# pi_pcb.net
KiCad netlist of a schematic drawn in EAGLE
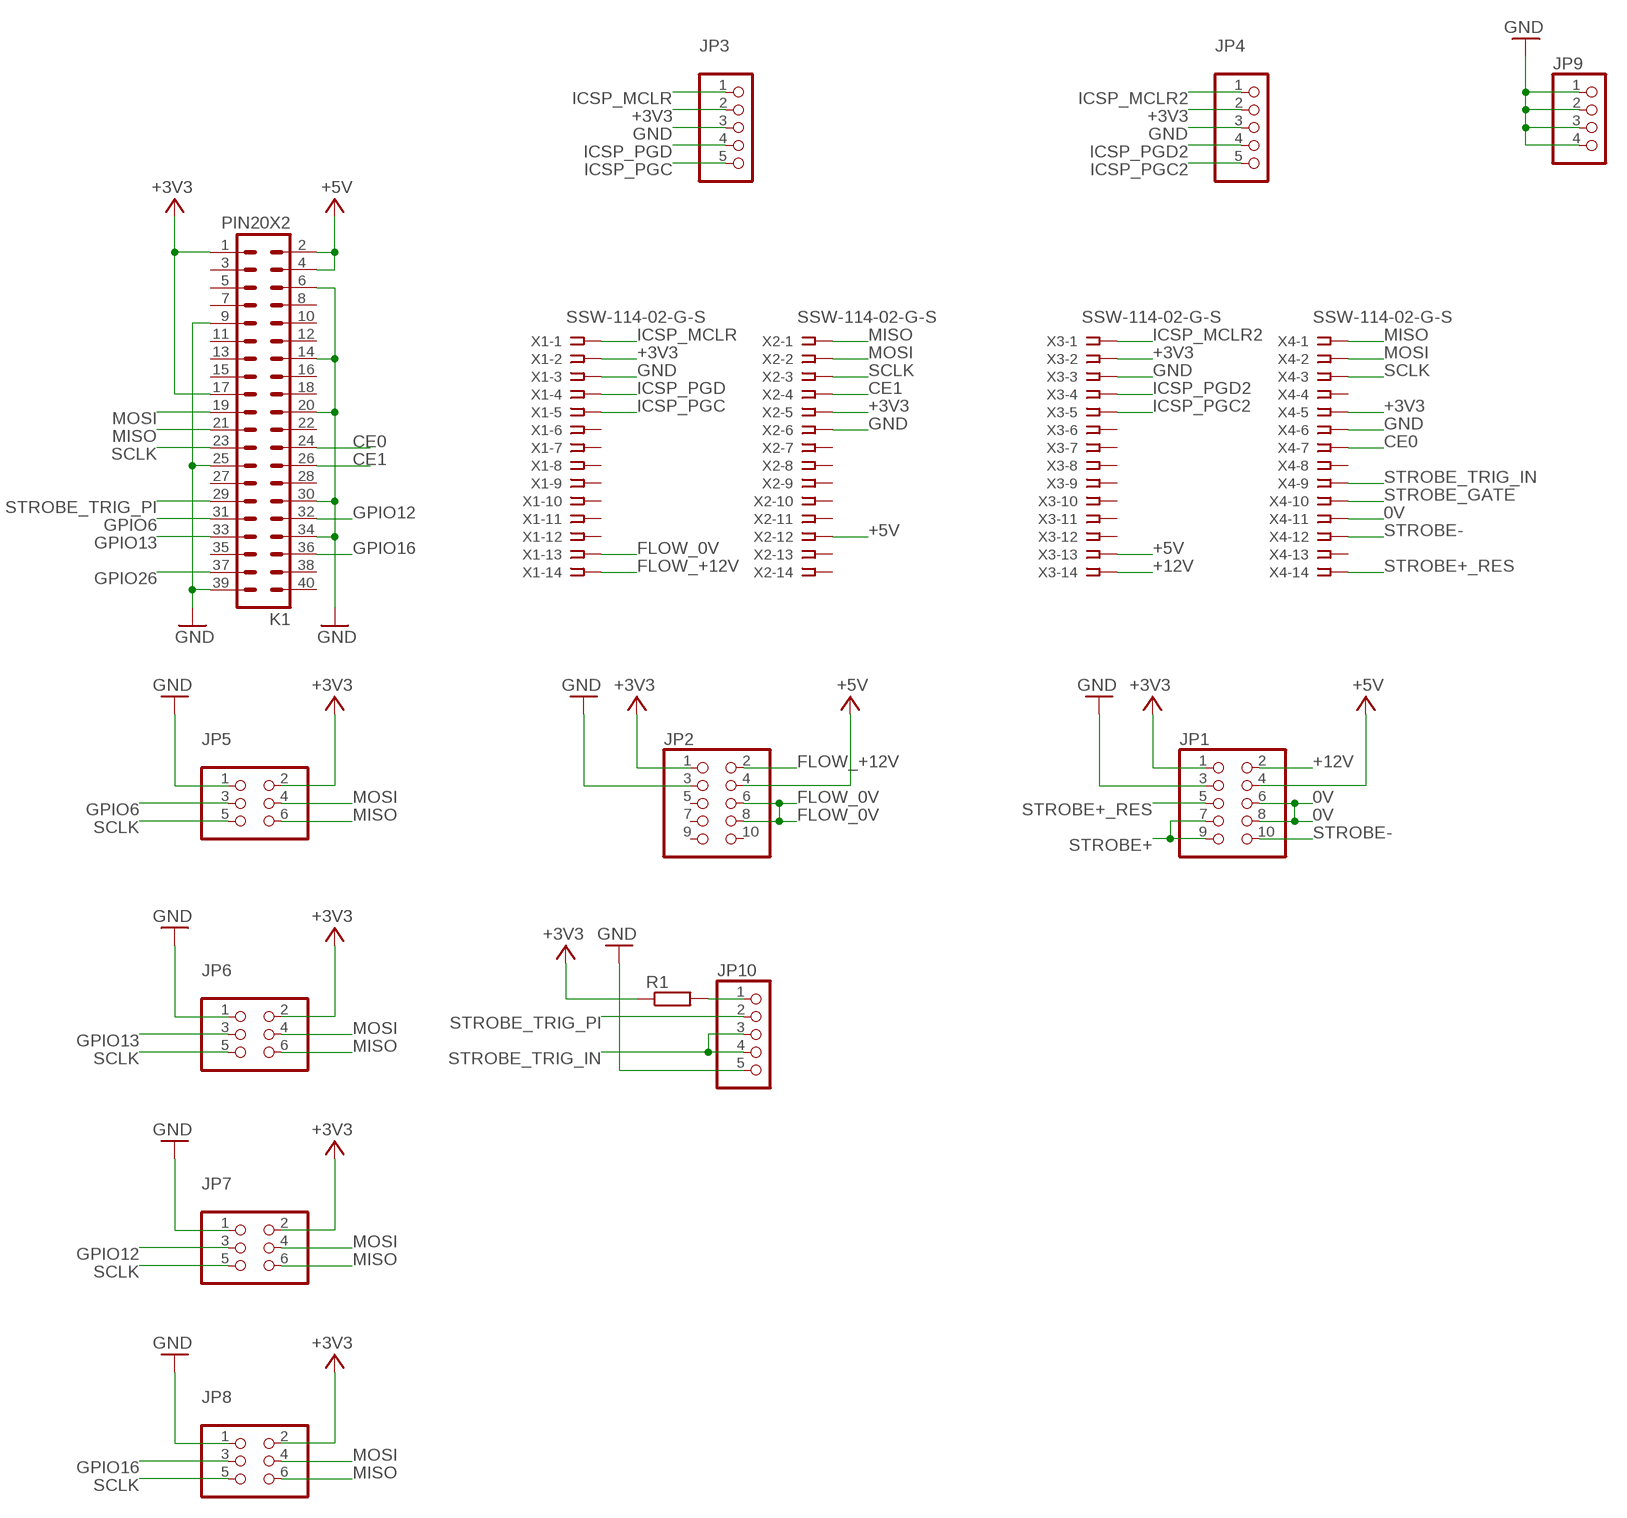
[diagram p0: schematic, sheet 1]

(export (version "E")
  (design (tool "Eeschema 10.0.6"))
  (components
    (comp (ref "JP1")
      (value "PINHD-2X5")
      (footprint "eagle-import:2X05")
      (libsource (lib "eagle-import") (part "PINHD-2X5"))
    )
    (comp (ref "JP2")
      (value "PINHD-2X5")
      (footprint "eagle-import:2X05")
      (libsource (lib "eagle-import") (part "PINHD-2X5"))
    )
    (comp (ref "JP3")
      (value "PINHD-1X5")
      (footprint "eagle-import:1X05")
      (libsource (lib "eagle-import") (part "PINHD-1X5"))
    )
    (comp (ref "JP4")
      (value "PINHD-1X5")
      (footprint "eagle-import:1X05")
      (libsource (lib "eagle-import") (part "PINHD-1X5"))
    )
    (comp (ref "JP5")
      (value "PINHD-2X3")
      (footprint "eagle-import:2X03")
      (libsource (lib "eagle-import") (part "PINHD-2X3"))
    )
    (comp (ref "JP6")
      (value "PINHD-2X3")
      (footprint "eagle-import:2X03")
      (libsource (lib "eagle-import") (part "PINHD-2X3"))
    )
    (comp (ref "JP7")
      (value "PINHD-2X3")
      (footprint "eagle-import:2X03")
      (libsource (lib "eagle-import") (part "PINHD-2X3"))
    )
    (comp (ref "JP8")
      (value "PINHD-2X3")
      (footprint "eagle-import:2X03")
      (libsource (lib "eagle-import") (part "PINHD-2X3"))
    )
    (comp (ref "JP9")
      (value "PINHD-1X4")
      (footprint "eagle-import:1X04")
      (libsource (lib "eagle-import") (part "PINHD-1X4"))
    )
    (comp (ref "JP10")
      (value "PINHD-1X5")
      (footprint "eagle-import:1X05")
      (libsource (lib "eagle-import") (part "PINHD-1X5"))
    )
    (comp (ref "K1")
      (value "PIN20X2")
      (footprint "eagle-import:PIN_20X2")
      (libsource (lib "eagle-import") (part "PIN20X2"))
    )
    (comp (ref "R1")
      (value "R-EU_R1206")
      (footprint "eagle-import:R1206")
      (libsource (lib "eagle-import") (part "R-EU_R1206"))
    )
    (comp (ref "X1")
      (value "SSW-114-02-G-S")
      (footprint "eagle-import:SSW-114-02-G-S")
      (fields (field (name "MF") "Samtec Inc."))
      (libsource (lib "eagle-import") (part "SSW-114-02-G-S"))
    )
    (comp (ref "X2")
      (value "SSW-114-02-G-S")
      (footprint "eagle-import:SSW-114-02-G-S")
      (fields (field (name "MF") "Samtec Inc."))
      (libsource (lib "eagle-import") (part "SSW-114-02-G-S"))
    )
    (comp (ref "X3")
      (value "SSW-114-02-G-S")
      (footprint "eagle-import:SSW-114-02-G-S")
      (fields (field (name "MF") "Samtec Inc."))
      (libsource (lib "eagle-import") (part "SSW-114-02-G-S"))
    )
    (comp (ref "X4")
      (value "SSW-114-02-G-S")
      (footprint "eagle-import:SSW-114-02-G-S")
      (fields (field (name "MF") "Samtec Inc."))
      (libsource (lib "eagle-import") (part "SSW-114-02-G-S"))
    )
  )
  (nets
    (net (code "1") (name "+3V3") (class "Default")
      (node (ref "JP1") (pin "1") (pinfunction "1_1") (pintype "passive"))
      (node (ref "JP2") (pin "1") (pinfunction "1_1") (pintype "passive"))
      (node (ref "JP3") (pin "2") (pinfunction "2_2") (pintype "passive"))
      (node (ref "JP4") (pin "2") (pinfunction "2_2") (pintype "passive"))
      (node (ref "JP5") (pin "2") (pinfunction "2_2") (pintype "passive"))
      (node (ref "JP6") (pin "2") (pinfunction "2_2") (pintype "passive"))
      (node (ref "JP7") (pin "2") (pinfunction "2_2") (pintype "passive"))
      (node (ref "JP8") (pin "2") (pinfunction "2_2") (pintype "passive"))
      (node (ref "K1") (pin "1") (pinfunction "1_1") (pintype "passive"))
      (node (ref "K1") (pin "17") (pinfunction "17_17") (pintype "passive"))
      (node (ref "R1") (pin "1") (pinfunction "1_1") (pintype "passive"))
      (node (ref "X1") (pin "2") (pinfunction "1_2") (pintype "passive"))
      (node (ref "X2") (pin "5") (pinfunction "1_5") (pintype "passive"))
      (node (ref "X3") (pin "2") (pinfunction "1_2") (pintype "passive"))
      (node (ref "X4") (pin "5") (pinfunction "1_5") (pintype "passive"))
    )
    (net (code "2") (name "+5V") (class "Default")
      (node (ref "JP1") (pin "4") (pinfunction "4_4") (pintype "passive"))
      (node (ref "JP2") (pin "4") (pinfunction "4_4") (pintype "passive"))
      (node (ref "K1") (pin "2") (pinfunction "2_2") (pintype "passive"))
      (node (ref "K1") (pin "4") (pinfunction "4_4") (pintype "passive"))
      (node (ref "X2") (pin "12") (pinfunction "1_12") (pintype "passive"))
      (node (ref "X3") (pin "13") (pinfunction "1_13") (pintype "passive"))
    )
    (net (code "3") (name "/+12V") (class "Default")
      (node (ref "JP1") (pin "2") (pinfunction "2_2") (pintype "passive"))
      (node (ref "X3") (pin "14") (pinfunction "1_14") (pintype "passive"))
    )
    (net (code "4") (name "/0V") (class "Default")
      (node (ref "JP1") (pin "6") (pinfunction "6_6") (pintype "passive"))
      (node (ref "JP1") (pin "8") (pinfunction "8_8") (pintype "passive"))
      (node (ref "X4") (pin "11") (pinfunction "1_11") (pintype "passive"))
    )
    (net (code "5") (name "/CE0") (class "Default")
      (node (ref "K1") (pin "24") (pinfunction "24_24") (pintype "passive"))
      (node (ref "X4") (pin "7") (pinfunction "1_7") (pintype "passive"))
    )
    (net (code "6") (name "/CE1") (class "Default")
      (node (ref "K1") (pin "26") (pinfunction "26_26") (pintype "passive"))
      (node (ref "X2") (pin "4") (pinfunction "1_4") (pintype "passive"))
    )
    (net (code "7") (name "/FLOW_+12V") (class "Default")
      (node (ref "JP2") (pin "2") (pinfunction "2_2") (pintype "passive"))
      (node (ref "X1") (pin "14") (pinfunction "1_14") (pintype "passive"))
    )
    (net (code "8") (name "/FLOW_0V") (class "Default")
      (node (ref "JP2") (pin "6") (pinfunction "6_6") (pintype "passive"))
      (node (ref "JP2") (pin "8") (pinfunction "8_8") (pintype "passive"))
      (node (ref "X1") (pin "13") (pinfunction "1_13") (pintype "passive"))
    )
    (net (code "9") (name "/GPIO6") (class "Default")
      (node (ref "JP5") (pin "3") (pinfunction "3_3") (pintype "passive"))
      (node (ref "K1") (pin "31") (pinfunction "31_31") (pintype "passive"))
    )
    (net (code "10") (name "/GPIO12") (class "Default")
      (node (ref "JP7") (pin "3") (pinfunction "3_3") (pintype "passive"))
      (node (ref "K1") (pin "32") (pinfunction "32_32") (pintype "passive"))
    )
    (net (code "11") (name "/GPIO13") (class "Default")
      (node (ref "JP6") (pin "3") (pinfunction "3_3") (pintype "passive"))
      (node (ref "K1") (pin "33") (pinfunction "33_33") (pintype "passive"))
    )
    (net (code "12") (name "/GPIO16") (class "Default")
      (node (ref "JP8") (pin "3") (pinfunction "3_3") (pintype "passive"))
      (node (ref "K1") (pin "36") (pinfunction "36_36") (pintype "passive"))
    )
    (net (code "13") (name "/GPIO26") (class "Default")
      (node (ref "K1") (pin "37") (pinfunction "37_37") (pintype "passive"))
    )
    (net (code "14") (name "/ICSP_MCLR") (class "Default")
      (node (ref "JP3") (pin "1") (pinfunction "1_1") (pintype "passive"))
      (node (ref "X1") (pin "1") (pinfunction "1_1") (pintype "passive"))
    )
    (net (code "15") (name "/ICSP_MCLR2") (class "Default")
      (node (ref "JP4") (pin "1") (pinfunction "1_1") (pintype "passive"))
      (node (ref "X3") (pin "1") (pinfunction "1_1") (pintype "passive"))
    )
    (net (code "16") (name "/ICSP_PGC") (class "Default")
      (node (ref "JP3") (pin "5") (pinfunction "5_5") (pintype "passive"))
      (node (ref "X1") (pin "5") (pinfunction "1_5") (pintype "passive"))
    )
    (net (code "17") (name "/ICSP_PGC2") (class "Default")
      (node (ref "JP4") (pin "5") (pinfunction "5_5") (pintype "passive"))
      (node (ref "X3") (pin "5") (pinfunction "1_5") (pintype "passive"))
    )
    (net (code "18") (name "/ICSP_PGD") (class "Default")
      (node (ref "JP3") (pin "4") (pinfunction "4_4") (pintype "passive"))
      (node (ref "X1") (pin "4") (pinfunction "1_4") (pintype "passive"))
    )
    (net (code "19") (name "/ICSP_PGD2") (class "Default")
      (node (ref "JP4") (pin "4") (pinfunction "4_4") (pintype "passive"))
      (node (ref "X3") (pin "4") (pinfunction "1_4") (pintype "passive"))
    )
    (net (code "20") (name "/MISO") (class "Default")
      (node (ref "JP5") (pin "6") (pinfunction "6_6") (pintype "passive"))
      (node (ref "JP6") (pin "6") (pinfunction "6_6") (pintype "passive"))
      (node (ref "JP7") (pin "6") (pinfunction "6_6") (pintype "passive"))
      (node (ref "JP8") (pin "6") (pinfunction "6_6") (pintype "passive"))
      (node (ref "K1") (pin "21") (pinfunction "21_21") (pintype "passive"))
      (node (ref "X2") (pin "1") (pinfunction "1_1") (pintype "passive"))
      (node (ref "X4") (pin "1") (pinfunction "1_1") (pintype "passive"))
    )
    (net (code "21") (name "/MOSI") (class "Default")
      (node (ref "JP5") (pin "4") (pinfunction "4_4") (pintype "passive"))
      (node (ref "JP6") (pin "4") (pinfunction "4_4") (pintype "passive"))
      (node (ref "JP7") (pin "4") (pinfunction "4_4") (pintype "passive"))
      (node (ref "JP8") (pin "4") (pinfunction "4_4") (pintype "passive"))
      (node (ref "K1") (pin "19") (pinfunction "19_19") (pintype "passive"))
      (node (ref "X2") (pin "2") (pinfunction "1_2") (pintype "passive"))
      (node (ref "X4") (pin "2") (pinfunction "1_2") (pintype "passive"))
    )
    (net (code "22") (name "/SCLK") (class "Default")
      (node (ref "JP5") (pin "5") (pinfunction "5_5") (pintype "passive"))
      (node (ref "JP6") (pin "5") (pinfunction "5_5") (pintype "passive"))
      (node (ref "JP7") (pin "5") (pinfunction "5_5") (pintype "passive"))
      (node (ref "JP8") (pin "5") (pinfunction "5_5") (pintype "passive"))
      (node (ref "K1") (pin "23") (pinfunction "23_23") (pintype "passive"))
      (node (ref "X2") (pin "3") (pinfunction "1_3") (pintype "passive"))
      (node (ref "X4") (pin "3") (pinfunction "1_3") (pintype "passive"))
    )
    (net (code "23") (name "/STROBE+") (class "Default")
      (node (ref "JP1") (pin "7") (pinfunction "7_7") (pintype "passive"))
      (node (ref "JP1") (pin "9") (pinfunction "9_9") (pintype "passive"))
    )
    (net (code "24") (name "/STROBE+_RES") (class "Default")
      (node (ref "JP1") (pin "5") (pinfunction "5_5") (pintype "passive"))
      (node (ref "X4") (pin "14") (pinfunction "1_14") (pintype "passive"))
    )
    (net (code "25") (name "/STROBE-") (class "Default")
      (node (ref "JP1") (pin "10") (pinfunction "10_10") (pintype "passive"))
      (node (ref "X4") (pin "12") (pinfunction "1_12") (pintype "passive"))
    )
    (net (code "26") (name "/STROBE_GATE") (class "Default")
      (node (ref "X4") (pin "10") (pinfunction "1_10") (pintype "passive"))
    )
    (net (code "27") (name "/STROBE_TRIG_IN") (class "Default")
      (node (ref "JP10") (pin "3") (pinfunction "3_3") (pintype "passive"))
      (node (ref "JP10") (pin "4") (pinfunction "4_4") (pintype "passive"))
      (node (ref "X4") (pin "9") (pinfunction "1_9") (pintype "passive"))
    )
    (net (code "28") (name "/STROBE_TRIG_PI") (class "Default")
      (node (ref "JP10") (pin "2") (pinfunction "2_2") (pintype "passive"))
      (node (ref "K1") (pin "29") (pinfunction "29_29") (pintype "passive"))
    )
    (net (code "29") (name "GND") (class "Default")
      (node (ref "JP1") (pin "3") (pinfunction "3_3") (pintype "passive"))
      (node (ref "JP10") (pin "5") (pinfunction "5_5") (pintype "passive"))
      (node (ref "JP2") (pin "3") (pinfunction "3_3") (pintype "passive"))
      (node (ref "JP3") (pin "3") (pinfunction "3_3") (pintype "passive"))
      (node (ref "JP4") (pin "3") (pinfunction "3_3") (pintype "passive"))
      (node (ref "JP5") (pin "1") (pinfunction "1_1") (pintype "passive"))
      (node (ref "JP6") (pin "1") (pinfunction "1_1") (pintype "passive"))
      (node (ref "JP7") (pin "1") (pinfunction "1_1") (pintype "passive"))
      (node (ref "JP8") (pin "1") (pinfunction "1_1") (pintype "passive"))
      (node (ref "JP9") (pin "1") (pinfunction "1_1") (pintype "passive"))
      (node (ref "JP9") (pin "2") (pinfunction "2_2") (pintype "passive"))
      (node (ref "JP9") (pin "3") (pinfunction "3_3") (pintype "passive"))
      (node (ref "JP9") (pin "4") (pinfunction "4_4") (pintype "passive"))
      (node (ref "K1") (pin "14") (pinfunction "14_14") (pintype "passive"))
      (node (ref "K1") (pin "20") (pinfunction "20_20") (pintype "passive"))
      (node (ref "K1") (pin "25") (pinfunction "25_25") (pintype "passive"))
      (node (ref "K1") (pin "30") (pinfunction "30_30") (pintype "passive"))
      (node (ref "K1") (pin "34") (pinfunction "34_34") (pintype "passive"))
      (node (ref "K1") (pin "39") (pinfunction "39_39") (pintype "passive"))
      (node (ref "K1") (pin "6") (pinfunction "6_6") (pintype "passive"))
      (node (ref "K1") (pin "9") (pinfunction "9_9") (pintype "passive"))
      (node (ref "X1") (pin "3") (pinfunction "1_3") (pintype "passive"))
      (node (ref "X2") (pin "6") (pinfunction "1_6") (pintype "passive"))
      (node (ref "X3") (pin "3") (pinfunction "1_3") (pintype "passive"))
      (node (ref "X4") (pin "6") (pinfunction "1_6") (pintype "passive"))
    )
    (net (code "30") (name "Net-(JP10-Pad1)") (class "Default")
      (node (ref "JP10") (pin "1") (pinfunction "1_1") (pintype "passive"))
      (node (ref "R1") (pin "2") (pinfunction "2_2") (pintype "passive"))
    )
    (net (code "31") (name "unconnected-(JP2-Pad5)") (class "Default")
      (node (ref "JP2") (pin "5") (pinfunction "5_5") (pintype "passive"))
    )
    (net (code "32") (name "unconnected-(JP2-Pad7)") (class "Default")
      (node (ref "JP2") (pin "7") (pinfunction "7_7") (pintype "passive"))
    )
    (net (code "33") (name "unconnected-(JP2-Pad9)") (class "Default")
      (node (ref "JP2") (pin "9") (pinfunction "9_9") (pintype "passive"))
    )
    (net (code "34") (name "unconnected-(JP2-Pad10)") (class "Default")
      (node (ref "JP2") (pin "10") (pinfunction "10_10") (pintype "passive"))
    )
    (net (code "35") (name "unconnected-(K1-Pad3)") (class "Default")
      (node (ref "K1") (pin "3") (pinfunction "3_3") (pintype "passive"))
    )
    (net (code "36") (name "unconnected-(K1-Pad5)") (class "Default")
      (node (ref "K1") (pin "5") (pinfunction "5_5") (pintype "passive"))
    )
    (net (code "37") (name "unconnected-(K1-Pad7)") (class "Default")
      (node (ref "K1") (pin "7") (pinfunction "7_7") (pintype "passive"))
    )
    (net (code "38") (name "unconnected-(K1-Pad8)") (class "Default")
      (node (ref "K1") (pin "8") (pinfunction "8_8") (pintype "passive"))
    )
    (net (code "39") (name "unconnected-(K1-Pad10)") (class "Default")
      (node (ref "K1") (pin "10") (pinfunction "10_10") (pintype "passive"))
    )
    (net (code "40") (name "unconnected-(K1-Pad11)") (class "Default")
      (node (ref "K1") (pin "11") (pinfunction "11_11") (pintype "passive"))
    )
    (net (code "41") (name "unconnected-(K1-Pad12)") (class "Default")
      (node (ref "K1") (pin "12") (pinfunction "12_12") (pintype "passive"))
    )
    (net (code "42") (name "unconnected-(K1-Pad13)") (class "Default")
      (node (ref "K1") (pin "13") (pinfunction "13_13") (pintype "passive"))
    )
    (net (code "43") (name "unconnected-(K1-Pad15)") (class "Default")
      (node (ref "K1") (pin "15") (pinfunction "15_15") (pintype "passive"))
    )
    (net (code "44") (name "unconnected-(K1-Pad16)") (class "Default")
      (node (ref "K1") (pin "16") (pinfunction "16_16") (pintype "passive"))
    )
    (net (code "45") (name "unconnected-(K1-Pad18)") (class "Default")
      (node (ref "K1") (pin "18") (pinfunction "18_18") (pintype "passive"))
    )
    (net (code "46") (name "unconnected-(K1-Pad22)") (class "Default")
      (node (ref "K1") (pin "22") (pinfunction "22_22") (pintype "passive"))
    )
    (net (code "47") (name "unconnected-(K1-Pad27)") (class "Default")
      (node (ref "K1") (pin "27") (pinfunction "27_27") (pintype "passive"))
    )
    (net (code "48") (name "unconnected-(K1-Pad28)") (class "Default")
      (node (ref "K1") (pin "28") (pinfunction "28_28") (pintype "passive"))
    )
    (net (code "49") (name "unconnected-(K1-Pad35)") (class "Default")
      (node (ref "K1") (pin "35") (pinfunction "35_35") (pintype "passive"))
    )
    (net (code "50") (name "unconnected-(K1-Pad38)") (class "Default")
      (node (ref "K1") (pin "38") (pinfunction "38_38") (pintype "passive"))
    )
    (net (code "51") (name "unconnected-(K1-Pad40)") (class "Default")
      (node (ref "K1") (pin "40") (pinfunction "40_40") (pintype "passive"))
    )
    (net (code "52") (name "unconnected-(X1B-1-Pad10)") (class "Default")
      (node (ref "X1") (pin "10") (pinfunction "1_10") (pintype "passive"))
    )
    (net (code "53") (name "unconnected-(X1C-1-Pad11)") (class "Default")
      (node (ref "X1") (pin "11") (pinfunction "1_11") (pintype "passive"))
    )
    (net (code "54") (name "unconnected-(X1D-1-Pad12)") (class "Default")
      (node (ref "X1") (pin "12") (pinfunction "1_12") (pintype "passive"))
    )
    (net (code "55") (name "unconnected-(X1K-1-Pad6)") (class "Default")
      (node (ref "X1") (pin "6") (pinfunction "1_6") (pintype "passive"))
    )
    (net (code "56") (name "unconnected-(X1L-1-Pad7)") (class "Default")
      (node (ref "X1") (pin "7") (pinfunction "1_7") (pintype "passive"))
    )
    (net (code "57") (name "unconnected-(X1M-1-Pad8)") (class "Default")
      (node (ref "X1") (pin "8") (pinfunction "1_8") (pintype "passive"))
    )
    (net (code "58") (name "unconnected-(X1N-1-Pad9)") (class "Default")
      (node (ref "X1") (pin "9") (pinfunction "1_9") (pintype "passive"))
    )
    (net (code "59") (name "unconnected-(X2B-1-Pad10)") (class "Default")
      (node (ref "X2") (pin "10") (pinfunction "1_10") (pintype "passive"))
    )
    (net (code "60") (name "unconnected-(X2C-1-Pad11)") (class "Default")
      (node (ref "X2") (pin "11") (pinfunction "1_11") (pintype "passive"))
    )
    (net (code "61") (name "unconnected-(X2E-1-Pad13)") (class "Default")
      (node (ref "X2") (pin "13") (pinfunction "1_13") (pintype "passive"))
    )
    (net (code "62") (name "unconnected-(X2F-1-Pad14)") (class "Default")
      (node (ref "X2") (pin "14") (pinfunction "1_14") (pintype "passive"))
    )
    (net (code "63") (name "unconnected-(X2L-1-Pad7)") (class "Default")
      (node (ref "X2") (pin "7") (pinfunction "1_7") (pintype "passive"))
    )
    (net (code "64") (name "unconnected-(X2M-1-Pad8)") (class "Default")
      (node (ref "X2") (pin "8") (pinfunction "1_8") (pintype "passive"))
    )
    (net (code "65") (name "unconnected-(X2N-1-Pad9)") (class "Default")
      (node (ref "X2") (pin "9") (pinfunction "1_9") (pintype "passive"))
    )
    (net (code "66") (name "unconnected-(X3B-1-Pad10)") (class "Default")
      (node (ref "X3") (pin "10") (pinfunction "1_10") (pintype "passive"))
    )
    (net (code "67") (name "unconnected-(X3C-1-Pad11)") (class "Default")
      (node (ref "X3") (pin "11") (pinfunction "1_11") (pintype "passive"))
    )
    (net (code "68") (name "unconnected-(X3D-1-Pad12)") (class "Default")
      (node (ref "X3") (pin "12") (pinfunction "1_12") (pintype "passive"))
    )
    (net (code "69") (name "unconnected-(X3K-1-Pad6)") (class "Default")
      (node (ref "X3") (pin "6") (pinfunction "1_6") (pintype "passive"))
    )
    (net (code "70") (name "unconnected-(X3L-1-Pad7)") (class "Default")
      (node (ref "X3") (pin "7") (pinfunction "1_7") (pintype "passive"))
    )
    (net (code "71") (name "unconnected-(X3M-1-Pad8)") (class "Default")
      (node (ref "X3") (pin "8") (pinfunction "1_8") (pintype "passive"))
    )
    (net (code "72") (name "unconnected-(X3N-1-Pad9)") (class "Default")
      (node (ref "X3") (pin "9") (pinfunction "1_9") (pintype "passive"))
    )
    (net (code "73") (name "unconnected-(X4E-1-Pad13)") (class "Default")
      (node (ref "X4") (pin "13") (pinfunction "1_13") (pintype "passive"))
    )
    (net (code "74") (name "unconnected-(X4I-1-Pad4)") (class "Default")
      (node (ref "X4") (pin "4") (pinfunction "1_4") (pintype "passive"))
    )
    (net (code "75") (name "unconnected-(X4M-1-Pad8)") (class "Default")
      (node (ref "X4") (pin "8") (pinfunction "1_8") (pintype "passive"))
    )
  )
)
